# Cyusb3014_-_4.net
KiCad netlist of a schematic drawn in Altium Designer
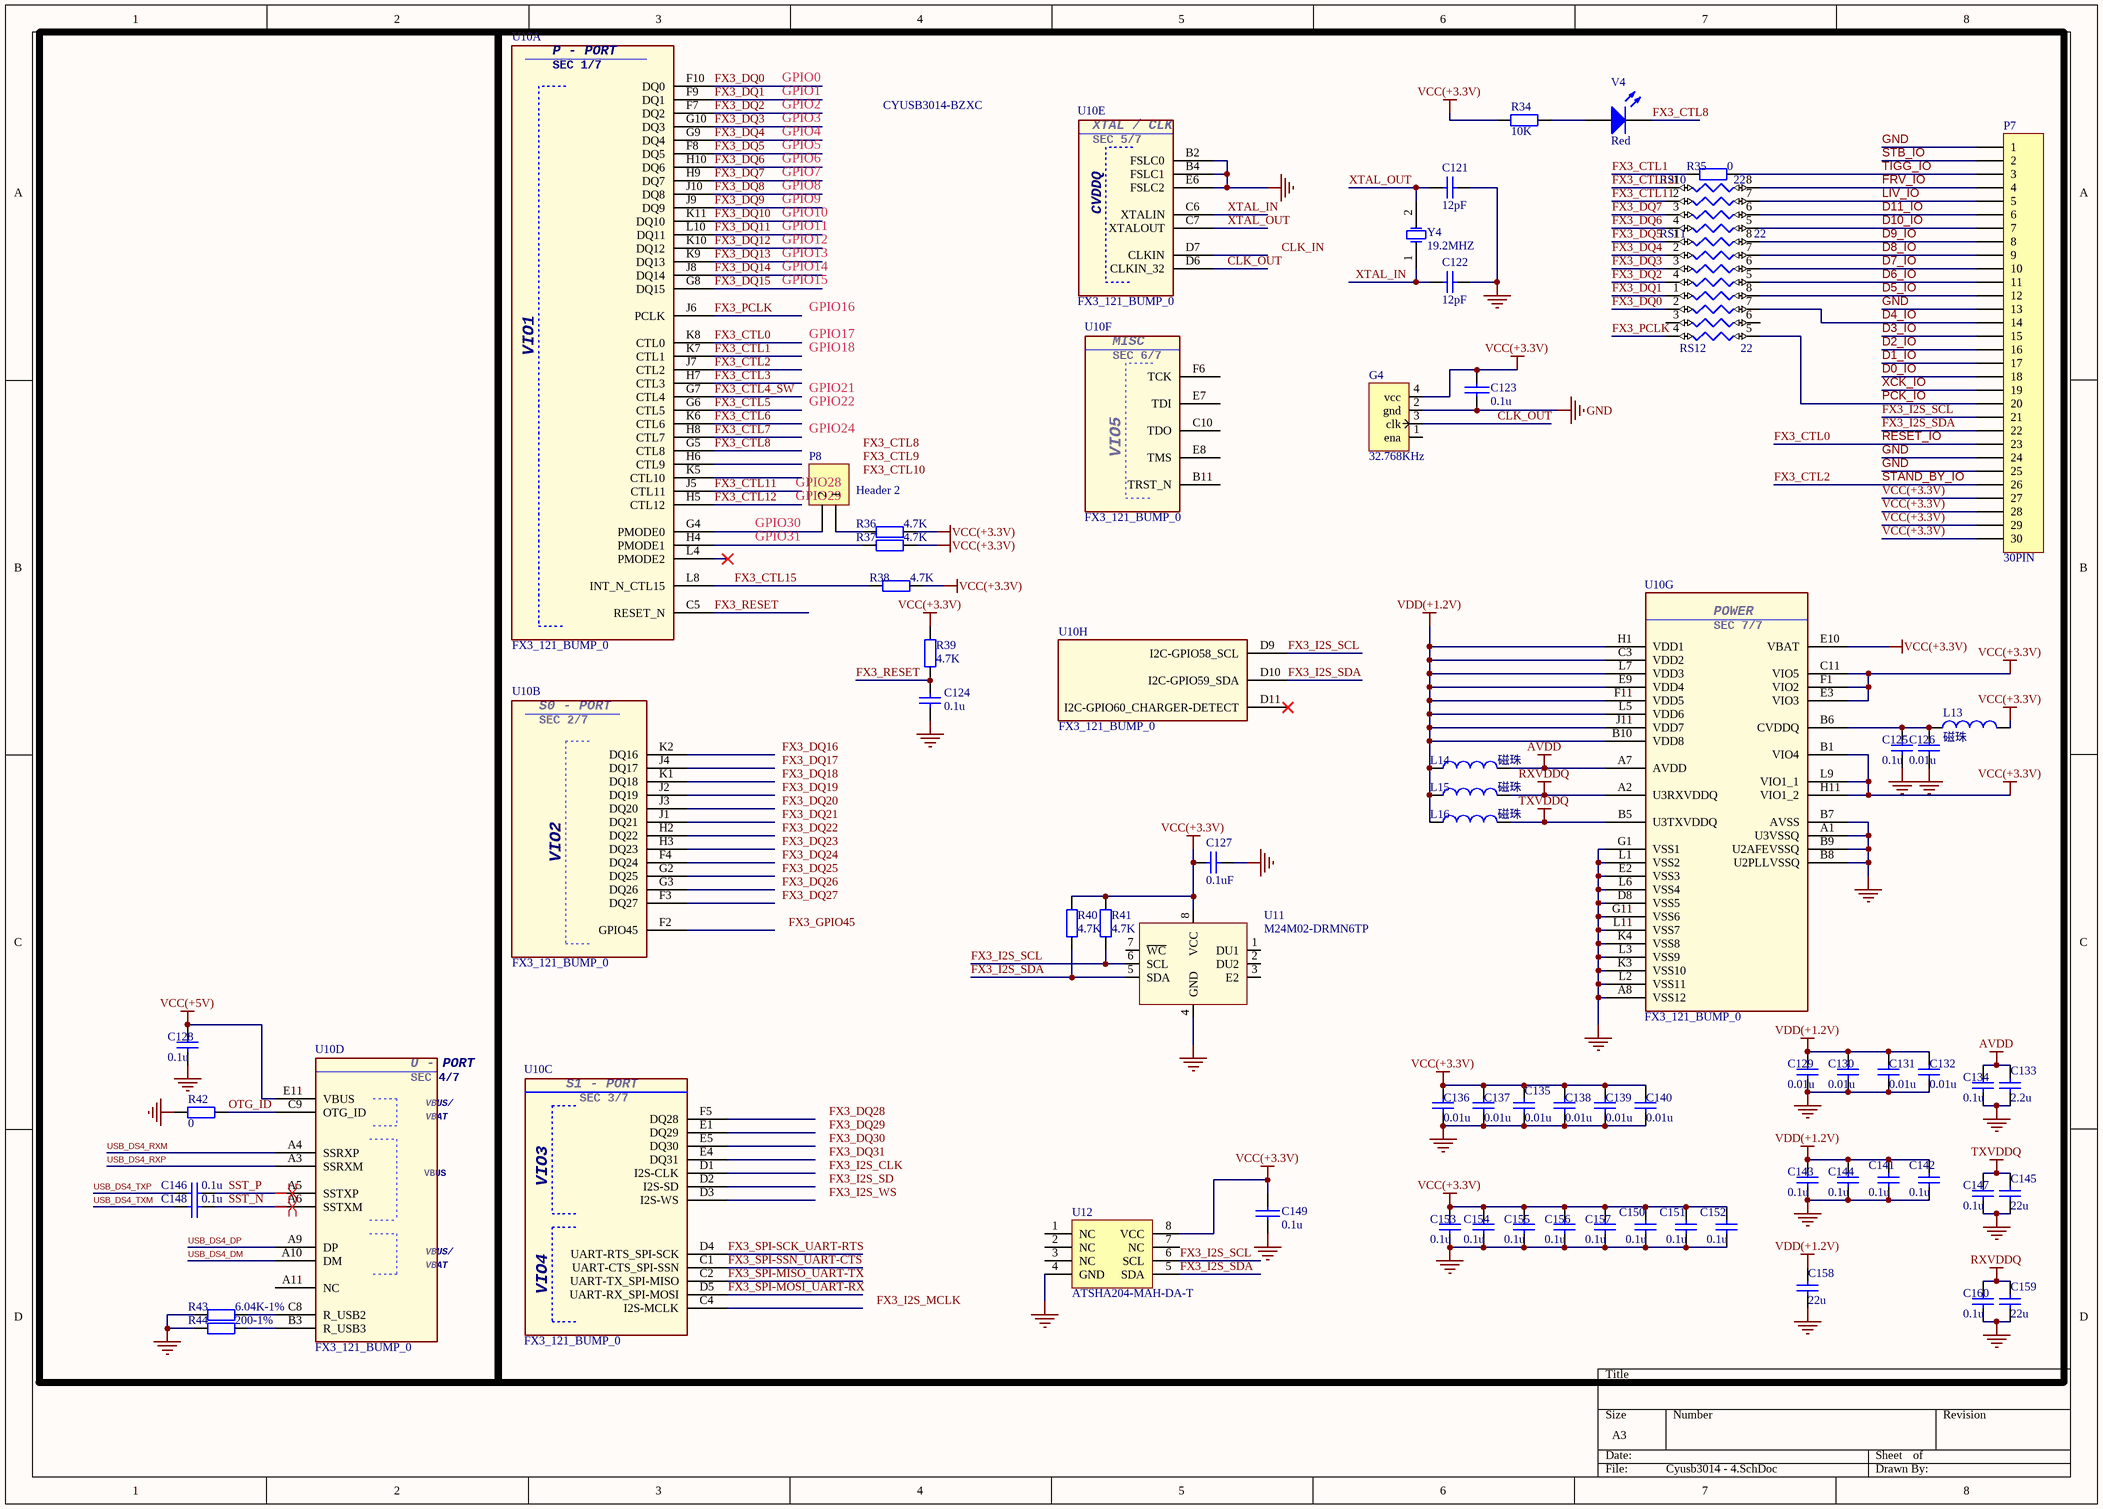
[diagram p0: Cyusb3014 - 4.SchDoc]

(export (version "E")
  (design (tool "Eeschema 10.0.6"))
  (components
    (comp (ref "C121")
      (value "12pF")
      (footprint "0603S-CAP")
      (description "CAP CER SMT 4.3pF 0805")
      (fields
        (field (name "2. MANUFACTURERE PART NUMBER") "C0805C439D5GACTU")
        (field (name "8. ALTERNATE PART") "any")
      )
      (libsource (lib "Peeple_eval") (part "CAP CER SMT 4.3pF 0805"))
    )
    (comp (ref "C122")
      (value "12pF")
      (footprint "0603S-CAP")
      (description "CAP CER SMT 4.3pF 0805")
      (fields
        (field (name "2. MANUFACTURERE PART NUMBER") "C0805C439D5GACTU")
        (field (name "8. ALTERNATE PART") "any")
      )
      (libsource (lib "Peeple_eval") (part "CAP CER SMT 4.3pF 0805"))
    )
    (comp (ref "C123")
      (value "0.1u")
      (footprint "0603S-CAP")
      (description "RC=1206")
      (libsource (lib "*") (part "CAP"))
    )
    (comp (ref "C124")
      (value "0.1u")
      (footprint "0603S-CAP")
      (description "50V/8.2u/0805")
      (fields (field (name "PUBLISHER") "Altium Limited"))
      (libsource (lib "Miscellaneous Devices") (part "Cap"))
    )
    (comp (ref "C125")
      (value "0.1u")
      (footprint "C0402")
      (description "Capacitor")
      (fields (field (name "PUBLISHER") "Altium Limited"))
      (libsource (lib "WM360") (part "CAP0805"))
    )
    (comp (ref "C126")
      (value "0.01u")
      (footprint "C0402")
      (description "Capacitor")
      (fields (field (name "PUBLISHER") "Altium Limited"))
      (libsource (lib "WM360") (part "CAP0805"))
    )
    (comp (ref "C127")
      (value "0.1uF")
      (footprint "0603S-CAP")
      (description "CAP SMT 0.1uF 16V X7R")
      (fields
        (field (name "2. MANUFACTURERE PART NUMBER") "C0805C104K4RACTU")
        (field (name "8. ALTERNATE PART") "any")
      )
      (libsource (lib "Peeple_eval") (part "CAP SMT 0.1uF 16V X7R"))
    )
    (comp (ref "C128")
      (value "0.1u")
      (footprint "C0402")
      (description "Capacitor")
      (fields (field (name "PUBLISHER") "Altium Limited"))
      (libsource (lib "WM360") (part "CAP0805"))
    )
    (comp (ref "C129")
      (value "0.01u")
      (footprint "C0402")
      (description "Capacitor")
      (fields (field (name "PUBLISHER") "Altium Limited"))
      (libsource (lib "WM360") (part "CAP0805"))
    )
    (comp (ref "C130")
      (value "0.01u")
      (footprint "C0402")
      (description "Capacitor")
      (fields (field (name "PUBLISHER") "Altium Limited"))
      (libsource (lib "WM360") (part "CAP0805"))
    )
    (comp (ref "C131")
      (value "0.01u")
      (footprint "C0402")
      (description "Capacitor")
      (fields (field (name "PUBLISHER") "Altium Limited"))
      (libsource (lib "WM360") (part "CAP0805"))
    )
    (comp (ref "C132")
      (value "0.01u")
      (footprint "C0402")
      (description "Capacitor")
      (fields (field (name "PUBLISHER") "Altium Limited"))
      (libsource (lib "WM360") (part "CAP0805"))
    )
    (comp (ref "C133")
      (value "2.2u")
      (footprint "C0805S-CAP")
      (description "Capacitor")
      (fields (field (name "PUBLISHER") "Altium Limited"))
      (libsource (lib "USB_CAMERA") (part "CAP0805"))
    )
    (comp (ref "C134")
      (value "0.1u")
      (footprint "C0402")
      (description "Capacitor")
      (fields (field (name "PUBLISHER") "Altium Limited"))
      (libsource (lib "WM360") (part "CAP0805"))
    )
    (comp (ref "C135")
      (value "0.01u")
      (footprint "C0402")
      (description "Capacitor")
      (fields (field (name "PUBLISHER") "Altium Limited"))
      (libsource (lib "WM360") (part "CAP0805"))
    )
    (comp (ref "C136")
      (value "0.01u")
      (footprint "C0402")
      (description "Capacitor")
      (fields (field (name "PUBLISHER") "Altium Limited"))
      (libsource (lib "WM360") (part "CAP0805"))
    )
    (comp (ref "C137")
      (value "0.01u")
      (footprint "C0402")
      (description "Capacitor")
      (fields (field (name "PUBLISHER") "Altium Limited"))
      (libsource (lib "WM360") (part "CAP0805"))
    )
    (comp (ref "C138")
      (value "0.01u")
      (footprint "C0402")
      (description "Capacitor")
      (fields (field (name "PUBLISHER") "Altium Limited"))
      (libsource (lib "WM360") (part "CAP0805"))
    )
    (comp (ref "C139")
      (value "0.01u")
      (footprint "C0402")
      (description "Capacitor")
      (fields (field (name "PUBLISHER") "Altium Limited"))
      (libsource (lib "WM360") (part "CAP0805"))
    )
    (comp (ref "C140")
      (value "0.01u")
      (footprint "C0402")
      (description "Capacitor")
      (fields (field (name "PUBLISHER") "Altium Limited"))
      (libsource (lib "WM360") (part "CAP0805"))
    )
    (comp (ref "C141")
      (value "0.1u")
      (footprint "C0402")
      (description "Capacitor")
      (fields (field (name "PUBLISHER") "Altium Limited"))
      (libsource (lib "WM360") (part "CAP0805"))
    )
    (comp (ref "C142")
      (value "0.1u")
      (footprint "C0402")
      (description "Capacitor")
      (fields (field (name "PUBLISHER") "Altium Limited"))
      (libsource (lib "WM360") (part "CAP0805"))
    )
    (comp (ref "C143")
      (value "0.1u")
      (footprint "C0402")
      (description "Capacitor")
      (fields (field (name "PUBLISHER") "Altium Limited"))
      (libsource (lib "WM360") (part "CAP0805"))
    )
    (comp (ref "C144")
      (value "0.1u")
      (footprint "C0402")
      (description "Capacitor")
      (fields (field (name "PUBLISHER") "Altium Limited"))
      (libsource (lib "WM360") (part "CAP0805"))
    )
    (comp (ref "C145")
      (value "22u")
      (footprint "C0805S-CAP")
      (description "Capacitor")
      (fields (field (name "PUBLISHER") "Altium Limited"))
      (libsource (lib "USB_CAMERA") (part "CAP0805"))
    )
    (comp (ref "C146")
      (value "0.1u")
      (footprint "C0402")
      (description "Capacitor")
      (fields (field (name "PUBLISHER") "Altium Limited"))
      (libsource (lib "WM360") (part "CAP0805"))
    )
    (comp (ref "C147")
      (value "0.1u")
      (footprint "C0402")
      (description "Capacitor")
      (fields (field (name "PUBLISHER") "Altium Limited"))
      (libsource (lib "WM360") (part "CAP0805"))
    )
    (comp (ref "C148")
      (value "0.1u")
      (footprint "C0402")
      (description "Capacitor")
      (fields (field (name "PUBLISHER") "Altium Limited"))
      (libsource (lib "WM360") (part "CAP0805"))
    )
    (comp (ref "C149")
      (value "0.1u")
      (footprint "0603S-CAP")
      (description "RC=1206")
      (libsource (lib "*") (part "CAP"))
    )
    (comp (ref "C150")
      (value "0.1u")
      (footprint "C0402")
      (description "Capacitor")
      (fields (field (name "PUBLISHER") "Altium Limited"))
      (libsource (lib "WM360") (part "CAP0805"))
    )
    (comp (ref "C151")
      (value "0.1u")
      (footprint "C0402")
      (description "Capacitor")
      (fields (field (name "PUBLISHER") "Altium Limited"))
      (libsource (lib "WM360") (part "CAP0805"))
    )
    (comp (ref "C152")
      (value "0.1u")
      (footprint "C0402")
      (description "Capacitor")
      (fields (field (name "PUBLISHER") "Altium Limited"))
      (libsource (lib "WM360") (part "CAP0805"))
    )
    (comp (ref "C153")
      (value "0.1u")
      (footprint "C0402")
      (description "Capacitor")
      (fields (field (name "PUBLISHER") "Altium Limited"))
      (libsource (lib "WM360") (part "CAP0805"))
    )
    (comp (ref "C154")
      (value "0.1u")
      (footprint "C0402")
      (description "Capacitor")
      (fields (field (name "PUBLISHER") "Altium Limited"))
      (libsource (lib "WM360") (part "CAP0805"))
    )
    (comp (ref "C155")
      (value "0.1u")
      (footprint "C0402")
      (description "Capacitor")
      (fields (field (name "PUBLISHER") "Altium Limited"))
      (libsource (lib "WM360") (part "CAP0805"))
    )
    (comp (ref "C156")
      (value "0.1u")
      (footprint "C0402")
      (description "Capacitor")
      (fields (field (name "PUBLISHER") "Altium Limited"))
      (libsource (lib "WM360") (part "CAP0805"))
    )
    (comp (ref "C157")
      (value "0.1u")
      (footprint "C0402")
      (description "Capacitor")
      (fields (field (name "PUBLISHER") "Altium Limited"))
      (libsource (lib "WM360") (part "CAP0805"))
    )
    (comp (ref "C158")
      (value "22u")
      (footprint "C0805S-CAP")
      (description "Capacitor")
      (fields (field (name "PUBLISHER") "Altium Limited"))
      (libsource (lib "USB_CAMERA") (part "CAP0805"))
    )
    (comp (ref "C159")
      (value "22u")
      (footprint "C0805S-CAP")
      (description "Capacitor")
      (fields (field (name "PUBLISHER") "Altium Limited"))
      (libsource (lib "USB_CAMERA") (part "CAP0805"))
    )
    (comp (ref "C160")
      (value "0.1u")
      (footprint "C0402")
      (description "Capacitor")
      (fields (field (name "PUBLISHER") "Altium Limited"))
      (libsource (lib "WM360") (part "CAP0805"))
    )
    (comp (ref "G4") (value "32.768KHz") (footprint "爱普生晶振3.2×2.5mm") (libsource (lib "*") (part "CTY4-B")))
    (comp (ref "L13")
      (value "磁珠")
      (footprint "L0603")
      (description "Inductor")
      (fields (field (name "PUBLISHER") "Altium Limited"))
      (libsource (lib "Miscellaneous Devices") (part "Inductor"))
    )
    (comp (ref "L14")
      (value "磁珠")
      (footprint "L0603")
      (description "Inductor")
      (fields (field (name "PUBLISHER") "Altium Limited"))
      (libsource (lib "Miscellaneous Devices") (part "Inductor"))
    )
    (comp (ref "L15")
      (value "磁珠")
      (footprint "L0603")
      (description "Inductor")
      (fields (field (name "PUBLISHER") "Altium Limited"))
      (libsource (lib "Miscellaneous Devices") (part "Inductor"))
    )
    (comp (ref "L16")
      (value "磁珠")
      (footprint "L0603")
      (description "Inductor")
      (fields (field (name "PUBLISHER") "Altium Limited"))
      (libsource (lib "Miscellaneous Devices") (part "Inductor"))
    )
    (comp (ref "P7")
      (value "30PIN")
      (footprint "FH12-30S-0.5SH")
      (description "Header, 30-Pin")
      (fields (field (name "PUBLISHER") "Altium Limited"))
      (libsource (lib "Miscellaneous Connectors") (part "Header 30"))
    )
    (comp (ref "P8")
      (value "Header 2")
      (footprint "HDR1X2")
      (description "Header, 2-Pin")
      (fields (field (name "PUBLISHER") "Altium Limited"))
      (libsource (lib "Miscellaneous Connectors") (part "Header 2"))
    )
    (comp (ref "R34")
      (value "10K")
      (footprint "0603S-RES")
      (description "Resistor")
      (fields (field (name "PUBLISHER") "Altium Limited"))
      (libsource (lib "DM642") (part "Res2"))
    )
    (comp (ref "R35")
      (value "0")
      (footprint "0603S-RES")
      (description "Resistor")
      (fields (field (name "PUBLISHER") "Altium Limited"))
      (libsource (lib "DM642") (part "Res2"))
    )
    (comp (ref "R36")
      (value "4.7K")
      (footprint "0603S-RES")
      (description "Resistor")
      (fields (field (name "PUBLISHER") "Altium Limited"))
      (libsource (lib "") (part "Res2_1"))
    )
    (comp (ref "R37")
      (value "4.7K")
      (footprint "0603S-RES")
      (description "Resistor")
      (fields (field (name "PUBLISHER") "Altium Limited"))
      (libsource (lib "") (part "Res2_1"))
    )
    (comp (ref "R38")
      (value "4.7K")
      (footprint "0603S-RES")
      (description "Resistor")
      (fields (field (name "PUBLISHER") "Altium Limited"))
      (libsource (lib "") (part "Res2_2"))
    )
    (comp (ref "R39")
      (value "4.7K")
      (footprint "0603S-RES")
      (description "Resistor")
      (fields (field (name "PUBLISHER") "Altium Limited"))
      (libsource (lib "") (part "Res2_3"))
    )
    (comp (ref "R40")
      (value "4.7K")
      (footprint "0603S-RES")
      (description "Resistor")
      (fields (field (name "PUBLISHER") "Altium Limited"))
      (libsource (lib "") (part "Res2_1"))
    )
    (comp (ref "R41")
      (value "4.7K")
      (footprint "0603S-RES")
      (description "Resistor")
      (fields (field (name "PUBLISHER") "Altium Limited"))
      (libsource (lib "") (part "Res2_1"))
    )
    (comp (ref "R42")
      (value "0")
      (footprint "0603S-RES")
      (description "Resistor")
      (fields (field (name "PUBLISHER") "Altium Limited"))
      (libsource (lib "") (part "Res2_2"))
    )
    (comp (ref "R43")
      (value "6.04K-1%")
      (footprint "0603S-RES")
      (description "Resistor")
      (fields (field (name "PUBLISHER") "Altium Limited"))
      (libsource (lib "") (part "Res2_2"))
    )
    (comp (ref "R44")
      (value "200-1%")
      (footprint "0603S-RES")
      (description "Resistor")
      (fields (field (name "PUBLISHER") "Altium Limited"))
      (libsource (lib "") (part "Res2_2"))
    )
    (comp (ref "RS10") (value "22") (footprint "NC06-4") (libsource (lib "*") (part "RN4")))
    (comp (ref "RS11") (value "22") (footprint "NC06-4") (libsource (lib "*") (part "RN4")))
    (comp (ref "RS12") (value "22") (footprint "NC06-4") (libsource (lib "*") (part "RN4")))
    (comp (ref "U10")
      (value "FX3_121_BUMP_0")
      (footprint "121_BGA_FX3")
      (libsource (lib "USB_CAMERA") (part "FX3_121_BUMP_0"))
    )
    (comp (ref "U11")
      (value "M24M02-DRMN6TP")
      (footprint "SOIC127P600X175-8N")
      (description "IC EEPROM 64KBIT 400KHZ 8SOIC")
      (fields
        (field (name "MANUFACTURER") "Microchip Technology")
        (field (name "MANUFACTURER PART NUMBER") "24LC64-I/SN")
      )
      (libsource (lib "Schlib1") (part "24LC64-I/SN"))
    )
    (comp (ref "U12")
      (value "ATSHA204-MAH-DA-T")
      (footprint "UDFN")
      (libsource (lib "CY7C68013-56") (part "AT24C128"))
    )
    (comp (ref "V4")
      (value "Red")
      (footprint "LED0805S")
      (description "Typical INFRARED GaAs LED")
      (fields (field (name "PUBLISHER") "Altium Limited"))
      (libsource (lib "DM642") (part "LED0"))
    )
    (comp (ref "Y4")
      (value "19.2MHZ")
      (footprint "爱普生晶振3.2×2.5MM - 无源")
      (description "Crystal, CRYSTAL 32.768KHZ 6PF SMD")
      (fields
        (field (name "2. MANUFACTURERE PART NUMBER") "ABS07-120-32.768KHZ-T")
        (field (name "4. SUPPLIER PART NUMBER") "535-11937-1-ND")
      )
      (libsource (lib "Peeple_eval") (part "XTAL 32.768KHZ"))
    )
  )
  (nets
    (net (code "2") (name "/CLK_OUT") (class "Default")
      (node (ref "G4") (pin "3") (pinfunction "clk_3") (pintype "passive"))
      (node (ref "U10") (pin "D6") (pinfunction "CLKIN_32_D6") (pintype "passive"))
    )
    (net (code "3") (name "/D0_IO") (class "Default")
      (node (ref "P7") (pin "18") (pinfunction "18_18") (pintype "passive"))
    )
    (net (code "4") (name "/D1_IO") (class "Default")
      (node (ref "P7") (pin "17") (pinfunction "17_17") (pintype "passive"))
    )
    (net (code "5") (name "/D2_IO") (class "Default")
      (node (ref "P7") (pin "16") (pinfunction "16_16") (pintype "passive"))
    )
    (net (code "6") (name "/D3_IO") (class "Default")
      (node (ref "P7") (pin "15") (pinfunction "15_15") (pintype "passive"))
    )
    (net (code "7") (name "/D4_IO") (class "Default")
      (node (ref "P7") (pin "14") (pinfunction "14_14") (pintype "passive"))
      (node (ref "RS12") (pin "7") (pinfunction "7_7") (pintype "bidirectional"))
    )
    (net (code "8") (name "/D5_IO") (class "Default")
      (node (ref "P7") (pin "12") (pinfunction "12_12") (pintype "passive"))
      (node (ref "RS12") (pin "8") (pinfunction "8_8") (pintype "bidirectional"))
    )
    (net (code "9") (name "/D6_IO") (class "Default")
      (node (ref "P7") (pin "11") (pinfunction "11_11") (pintype "passive"))
      (node (ref "RS11") (pin "5") (pinfunction "5_5") (pintype "bidirectional"))
    )
    (net (code "10") (name "/D7_IO") (class "Default")
      (node (ref "P7") (pin "10") (pinfunction "10_10") (pintype "passive"))
      (node (ref "RS11") (pin "6") (pinfunction "6_6") (pintype "bidirectional"))
    )
    (net (code "11") (name "/D8_IO") (class "Default")
      (node (ref "P7") (pin "9") (pinfunction "9_9") (pintype "passive"))
      (node (ref "RS11") (pin "7") (pinfunction "7_7") (pintype "bidirectional"))
    )
    (net (code "12") (name "/D9_IO") (class "Default")
      (node (ref "P7") (pin "8") (pinfunction "8_8") (pintype "passive"))
      (node (ref "RS11") (pin "8") (pinfunction "8_8") (pintype "bidirectional"))
    )
    (net (code "13") (name "/D10_IO") (class "Default")
      (node (ref "P7") (pin "7") (pinfunction "7_7") (pintype "passive"))
      (node (ref "RS10") (pin "5") (pinfunction "5_5") (pintype "bidirectional"))
    )
    (net (code "14") (name "/D11_IO") (class "Default")
      (node (ref "P7") (pin "6") (pinfunction "6_6") (pintype "passive"))
      (node (ref "RS10") (pin "6") (pinfunction "6_6") (pintype "bidirectional"))
    )
    (net (code "15") (name "/FRV_IO") (class "Default")
      (node (ref "P7") (pin "4") (pinfunction "4_4") (pintype "passive"))
      (node (ref "RS10") (pin "8") (pinfunction "8_8") (pintype "bidirectional"))
    )
    (net (code "16") (name "/FX3_CTL0") (class "Default")
      (node (ref "P7") (pin "23") (pinfunction "23_23") (pintype "passive"))
      (node (ref "U10") (pin "K8") (pinfunction "CTL0_K8") (pintype "passive"))
    )
    (net (code "17") (name "/FX3_CTL1") (class "Default")
      (node (ref "R35") (pin "2") (pinfunction "2_2") (pintype "passive"))
      (node (ref "U10") (pin "K7") (pinfunction "CTL1_K7") (pintype "passive"))
    )
    (net (code "18") (name "/FX3_CTL2") (class "Default")
      (node (ref "P7") (pin "26") (pinfunction "26_26") (pintype "passive"))
      (node (ref "U10") (pin "J7") (pinfunction "CTL2_J7") (pintype "passive"))
    )
    (net (code "19") (name "/FX3_CTL3") (class "Default")
      (node (ref "U10") (pin "H7") (pinfunction "CTL3_H7") (pintype "passive"))
    )
    (net (code "20") (name "/FX3_CTL4_SW") (class "Default")
      (node (ref "U10") (pin "G7") (pinfunction "CTL4_G7") (pintype "passive"))
    )
    (net (code "21") (name "/FX3_CTL5") (class "Default")
      (node (ref "U10") (pin "G6") (pinfunction "CTL5_G6") (pintype "passive"))
    )
    (net (code "22") (name "/FX3_CTL6") (class "Default")
      (node (ref "U10") (pin "K6") (pinfunction "CTL6_K6") (pintype "passive"))
    )
    (net (code "23") (name "/FX3_CTL7") (class "Default")
      (node (ref "U10") (pin "H8") (pinfunction "CTL7_H8") (pintype "passive"))
    )
    (net (code "24") (name "/FX3_CTL8") (class "Default")
      (node (ref "U10") (pin "G5") (pinfunction "CTL8_G5") (pintype "passive"))
      (node (ref "V4") (pin "2") (pinfunction "K_2") (pintype "passive"))
    )
    (net (code "27") (name "/FX3_CTL11") (class "Default")
      (node (ref "RS10") (pin "2") (pinfunction "2_2") (pintype "bidirectional"))
      (node (ref "U10") (pin "J5") (pinfunction "CTL11_J5") (pintype "passive"))
    )
    (net (code "28") (name "/FX3_CTL12") (class "Default")
      (node (ref "RS10") (pin "1") (pinfunction "1_1") (pintype "bidirectional"))
      (node (ref "U10") (pin "H5") (pinfunction "CTL12_H5") (pintype "passive"))
    )
    (net (code "29") (name "/FX3_CTL15") (class "Default")
      (node (ref "R38") (pin "2") (pinfunction "2_2") (pintype "passive"))
      (node (ref "U10") (pin "L8") (pinfunction "INT_N_CTL15_L8") (pintype "passive"))
    )
    (net (code "30") (name "/FX3_DQ0") (class "Default")
      (node (ref "RS12") (pin "2") (pinfunction "2_2") (pintype "bidirectional"))
      (node (ref "U10") (pin "F10") (pinfunction "DQ0_F10") (pintype "passive"))
    )
    (net (code "31") (name "/FX3_DQ1") (class "Default")
      (node (ref "RS12") (pin "1") (pinfunction "1_1") (pintype "bidirectional"))
      (node (ref "U10") (pin "F9") (pinfunction "DQ1_F9") (pintype "passive"))
    )
    (net (code "32") (name "/FX3_DQ2") (class "Default")
      (node (ref "RS11") (pin "4") (pinfunction "4_4") (pintype "bidirectional"))
      (node (ref "U10") (pin "F7") (pinfunction "DQ2_F7") (pintype "passive"))
    )
    (net (code "33") (name "/FX3_DQ3") (class "Default")
      (node (ref "RS11") (pin "3") (pinfunction "3_3") (pintype "bidirectional"))
      (node (ref "U10") (pin "G10") (pinfunction "DQ3_G10") (pintype "passive"))
    )
    (net (code "34") (name "/FX3_DQ4") (class "Default")
      (node (ref "RS11") (pin "2") (pinfunction "2_2") (pintype "bidirectional"))
      (node (ref "U10") (pin "G9") (pinfunction "DQ4_G9") (pintype "passive"))
    )
    (net (code "35") (name "/FX3_DQ5") (class "Default")
      (node (ref "RS11") (pin "1") (pinfunction "1_1") (pintype "bidirectional"))
      (node (ref "U10") (pin "F8") (pinfunction "DQ5_F8") (pintype "passive"))
    )
    (net (code "36") (name "/FX3_DQ6") (class "Default")
      (node (ref "RS10") (pin "4") (pinfunction "4_4") (pintype "bidirectional"))
      (node (ref "U10") (pin "H10") (pinfunction "DQ6_H10") (pintype "passive"))
    )
    (net (code "37") (name "/FX3_DQ7") (class "Default")
      (node (ref "RS10") (pin "3") (pinfunction "3_3") (pintype "bidirectional"))
      (node (ref "U10") (pin "H9") (pinfunction "DQ7_H9") (pintype "passive"))
    )
    (net (code "38") (name "/FX3_DQ8") (class "Default")
      (node (ref "U10") (pin "J10") (pinfunction "DQ8_J10") (pintype "passive"))
    )
    (net (code "39") (name "/FX3_DQ9") (class "Default")
      (node (ref "U10") (pin "J9") (pinfunction "DQ9_J9") (pintype "passive"))
    )
    (net (code "40") (name "/FX3_DQ10") (class "Default")
      (node (ref "U10") (pin "K11") (pinfunction "DQ10_K11") (pintype "passive"))
    )
    (net (code "41") (name "/FX3_DQ11") (class "Default")
      (node (ref "U10") (pin "L10") (pinfunction "DQ11_L10") (pintype "passive"))
    )
    (net (code "42") (name "/FX3_DQ12") (class "Default")
      (node (ref "U10") (pin "K10") (pinfunction "DQ12_K10") (pintype "passive"))
    )
    (net (code "43") (name "/FX3_DQ13") (class "Default")
      (node (ref "U10") (pin "K9") (pinfunction "DQ13_K9") (pintype "passive"))
    )
    (net (code "44") (name "/FX3_DQ14") (class "Default")
      (node (ref "U10") (pin "J8") (pinfunction "DQ14_J8") (pintype "passive"))
    )
    (net (code "45") (name "/FX3_DQ15") (class "Default")
      (node (ref "U10") (pin "G8") (pinfunction "DQ15_G8") (pintype "passive"))
    )
    (net (code "65") (name "/FX3_I2S_SCL") (class "Default")
      (node (ref "P7") (pin "21") (pinfunction "21_21") (pintype "passive"))
      (node (ref "R41") (pin "1") (pinfunction "1_1") (pintype "passive"))
      (node (ref "U10") (pin "D9") (pinfunction "I2C-GPIO58_SCL_D9") (pintype "passive"))
      (node (ref "U11") (pin "6") (pinfunction "SCL_6") (pintype "passive"))
      (node (ref "U12") (pin "6") (pinfunction "SCL_6") (pintype "passive"))
    )
    (net (code "67") (name "/FX3_I2S_SDA") (class "Default")
      (node (ref "P7") (pin "22") (pinfunction "22_22") (pintype "passive"))
      (node (ref "R40") (pin "1") (pinfunction "1_1") (pintype "passive"))
      (node (ref "U10") (pin "D10") (pinfunction "I2C-GPIO59_SDA_D10") (pintype "passive"))
      (node (ref "U11") (pin "5") (pinfunction "SDA_5") (pintype "passive"))
      (node (ref "U12") (pin "5") (pinfunction "SDA_5") (pintype "passive"))
    )
    (net (code "69") (name "/FX3_PCLK") (class "Default")
      (node (ref "RS12") (pin "4") (pinfunction "4_4") (pintype "bidirectional"))
      (node (ref "U10") (pin "J6") (pinfunction "PCLK_J6") (pintype "passive"))
    )
    (net (code "70") (name "/FX3_RESET") (class "Default")
      (node (ref "C124") (pin "2") (pinfunction "2_2") (pintype "passive"))
      (node (ref "R39") (pin "2") (pinfunction "2_2") (pintype "passive"))
      (node (ref "U10") (pin "C5") (pinfunction "RESET_N_C5") (pintype "passive"))
    )
    (net (code "71") (name "/FX3_SPI-MISO_UART-TX") (class "Default")
      (node (ref "U10") (pin "C2") (pinfunction "UART-TX_SPI-MISO_C2") (pintype "passive"))
    )
    (net (code "72") (name "/FX3_SPI-MOSI_UART-RX") (class "Default")
      (node (ref "U10") (pin "D5") (pinfunction "UART-RX_SPI-MOSI_D5") (pintype "passive"))
    )
    (net (code "73") (name "/FX3_SPI-SCK_UART-RTS") (class "Default")
      (node (ref "U10") (pin "D4") (pinfunction "UART-RTS_SPI-SCK_D4") (pintype "passive"))
    )
    (net (code "74") (name "/FX3_SPI-SSN_UART-CTS") (class "Default")
      (node (ref "U10") (pin "C1") (pinfunction "UART-CTS_SPI-SSN_C1") (pintype "passive"))
    )
    (net (code "75") (name "/LIV_IO") (class "Default")
      (node (ref "P7") (pin "5") (pinfunction "5_5") (pintype "passive"))
      (node (ref "RS10") (pin "7") (pinfunction "7_7") (pintype "bidirectional"))
    )
    (net (code "76") (name "/OTG_ID") (class "Default")
      (node (ref "R42") (pin "1") (pinfunction "1_1") (pintype "passive"))
      (node (ref "U10") (pin "C9") (pinfunction "OTG_ID_C9") (pintype "passive"))
    )
    (net (code "77") (name "/PCK_IO") (class "Default")
      (node (ref "P7") (pin "20") (pinfunction "20_20") (pintype "passive"))
      (node (ref "RS12") (pin "5") (pinfunction "5_5") (pintype "bidirectional"))
    )
    (net (code "78") (name "/SST_N") (class "Default")
      (node (ref "C148") (pin "2") (pinfunction "2_2") (pintype "passive"))
      (node (ref "U10") (pin "A6") (pinfunction "SSTXM_A6") (pintype "passive"))
    )
    (net (code "79") (name "/SST_P") (class "Default")
      (node (ref "C146") (pin "2") (pinfunction "2_2") (pintype "passive"))
      (node (ref "U10") (pin "A5") (pinfunction "SSTXP_A5") (pintype "passive"))
    )
    (net (code "80") (name "/STB_IO") (class "Default")
      (node (ref "P7") (pin "2") (pinfunction "2_2") (pintype "passive"))
    )
    (net (code "81") (name "/TIGG_IO") (class "Default")
      (node (ref "P7") (pin "3") (pinfunction "3_3") (pintype "passive"))
      (node (ref "R35") (pin "1") (pinfunction "1_1") (pintype "passive"))
    )
    (net (code "82") (name "/USB_DS4_DM") (class "Default")
      (node (ref "U10") (pin "A10") (pinfunction "DM_A10") (pintype "passive"))
    )
    (net (code "83") (name "/USB_DS4_DP") (class "Default")
      (node (ref "U10") (pin "A9") (pinfunction "DP_A9") (pintype "passive"))
    )
    (net (code "84") (name "/USB_DS4_RXM") (class "Default")
      (node (ref "U10") (pin "A4") (pinfunction "SSRXP_A4") (pintype "passive"))
    )
    (net (code "85") (name "/USB_DS4_RXP") (class "Default")
      (node (ref "U10") (pin "A3") (pinfunction "SSRXM_A3") (pintype "passive"))
    )
    (net (code "86") (name "/USB_DS4_TXM") (class "Default")
      (node (ref "C148") (pin "1") (pinfunction "1_1") (pintype "passive"))
    )
    (net (code "87") (name "/USB_DS4_TXP") (class "Default")
      (node (ref "C146") (pin "1") (pinfunction "1_1") (pintype "passive"))
    )
    (net (code "88") (name "/XCK_IO") (class "Default")
      (node (ref "P7") (pin "19") (pinfunction "19_19") (pintype "passive"))
    )
    (net (code "89") (name "/XTAL_IN") (class "Default")
      (node (ref "C122") (pin "2") (pinfunction "2_2") (pintype "passive"))
      (node (ref "U10") (pin "C6") (pinfunction "XTALIN_C6") (pintype "passive"))
      (node (ref "Y4") (pin "1") (pinfunction "OSC1_1") (pintype "passive"))
    )
    (net (code "90") (name "/XTAL_OUT") (class "Default")
      (node (ref "C121") (pin "2") (pinfunction "2_2") (pintype "passive"))
      (node (ref "U10") (pin "C7") (pinfunction "XTALOUT_C7") (pintype "passive"))
      (node (ref "Y4") (pin "2") (pinfunction "OSC2_2") (pintype "passive"))
    )
    (net (code "91") (name "AVDD") (class "Default")
      (node (ref "C133") (pin "2") (pinfunction "2_2") (pintype "passive"))
      (node (ref "C134") (pin "1") (pinfunction "1_1") (pintype "passive"))
      (node (ref "L14") (pin "2") (pinfunction "2_2") (pintype "passive"))
      (node (ref "U10") (pin "A7") (pinfunction "AVDD_A7") (pintype "passive"))
    )
    (net (code "92") (name "GND") (class "Default")
      (node (ref "C121") (pin "1") (pinfunction "1_1") (pintype "passive"))
      (node (ref "C122") (pin "1") (pinfunction "1_1") (pintype "passive"))
      (node (ref "C123") (pin "2") (pintype "passive"))
      (node (ref "C124") (pin "1") (pinfunction "1_1") (pintype "passive"))
      (node (ref "C125") (pin "2") (pinfunction "2_2") (pintype "passive"))
      (node (ref "C126") (pin "2") (pinfunction "2_2") (pintype "passive"))
      (node (ref "C127") (pin "1") (pinfunction "1_1") (pintype "passive"))
      (node (ref "C128") (pin "2") (pinfunction "2_2") (pintype "passive"))
      (node (ref "C129") (pin "2") (pinfunction "2_2") (pintype "passive"))
      (node (ref "C130") (pin "2") (pinfunction "2_2") (pintype "passive"))
      (node (ref "C131") (pin "2") (pinfunction "2_2") (pintype "passive"))
      (node (ref "C132") (pin "2") (pinfunction "2_2") (pintype "passive"))
      (node (ref "C133") (pin "1") (pinfunction "1_1") (pintype "passive"))
      (node (ref "C134") (pin "2") (pinfunction "2_2") (pintype "passive"))
      (node (ref "C135") (pin "2") (pinfunction "2_2") (pintype "passive"))
      (node (ref "C136") (pin "2") (pinfunction "2_2") (pintype "passive"))
      (node (ref "C137") (pin "2") (pinfunction "2_2") (pintype "passive"))
      (node (ref "C138") (pin "2") (pinfunction "2_2") (pintype "passive"))
      (node (ref "C139") (pin "2") (pinfunction "2_2") (pintype "passive"))
      (node (ref "C140") (pin "2") (pinfunction "2_2") (pintype "passive"))
      (node (ref "C141") (pin "2") (pinfunction "2_2") (pintype "passive"))
      (node (ref "C142") (pin "2") (pinfunction "2_2") (pintype "passive"))
      (node (ref "C143") (pin "2") (pinfunction "2_2") (pintype "passive"))
      (node (ref "C144") (pin "2") (pinfunction "2_2") (pintype "passive"))
      (node (ref "C145") (pin "1") (pinfunction "1_1") (pintype "passive"))
      (node (ref "C147") (pin "2") (pinfunction "2_2") (pintype "passive"))
      (node (ref "C149") (pin "2") (pintype "passive"))
      (node (ref "C150") (pin "2") (pinfunction "2_2") (pintype "passive"))
      (node (ref "C151") (pin "2") (pinfunction "2_2") (pintype "passive"))
      (node (ref "C152") (pin "2") (pinfunction "2_2") (pintype "passive"))
      (node (ref "C153") (pin "2") (pinfunction "2_2") (pintype "passive"))
      (node (ref "C154") (pin "2") (pinfunction "2_2") (pintype "passive"))
      (node (ref "C155") (pin "2") (pinfunction "2_2") (pintype "passive"))
      (node (ref "C156") (pin "2") (pinfunction "2_2") (pintype "passive"))
      (node (ref "C157") (pin "2") (pinfunction "2_2") (pintype "passive"))
      (node (ref "C158") (pin "1") (pinfunction "1_1") (pintype "passive"))
      (node (ref "C159") (pin "1") (pinfunction "1_1") (pintype "passive"))
      (node (ref "C160") (pin "2") (pinfunction "2_2") (pintype "passive"))
      (node (ref "G4") (pin "2") (pinfunction "gnd_2") (pintype "power_in"))
      (node (ref "P7") (pin "1") (pinfunction "1_1") (pintype "passive"))
      (node (ref "P7") (pin "13") (pinfunction "13_13") (pintype "passive"))
      (node (ref "P7") (pin "24") (pinfunction "24_24") (pintype "passive"))
      (node (ref "P7") (pin "25") (pinfunction "25_25") (pintype "passive"))
      (node (ref "R42") (pin "2") (pinfunction "2_2") (pintype "passive"))
      (node (ref "R43") (pin "2") (pinfunction "2_2") (pintype "passive"))
      (node (ref "R44") (pin "2") (pinfunction "2_2") (pintype "passive"))
      (node (ref "U10") (pin "A1") (pinfunction "U3VSSQ_A1") (pintype "passive"))
      (node (ref "U10") (pin "A8") (pinfunction "VSS12_A8") (pintype "passive"))
      (node (ref "U10") (pin "B2") (pinfunction "FSLC0_B2") (pintype "passive"))
      (node (ref "U10") (pin "B4") (pinfunction "FSLC1_B4") (pintype "passive"))
      (node (ref "U10") (pin "B7") (pinfunction "AVSS_B7") (pintype "passive"))
      (node (ref "U10") (pin "B8") (pinfunction "U2PLLVSSQ_B8") (pintype "passive"))
      (node (ref "U10") (pin "B9") (pinfunction "U2AFEVSSQ_B9") (pintype "passive"))
      (node (ref "U10") (pin "D8") (pinfunction "VSS5_D8") (pintype "passive"))
      (node (ref "U10") (pin "E2") (pinfunction "VSS3_E2") (pintype "passive"))
      (node (ref "U10") (pin "E6") (pinfunction "FSLC2_E6") (pintype "passive"))
      (node (ref "U10") (pin "G1") (pinfunction "VSS1_G1") (pintype "passive"))
      (node (ref "U10") (pin "G11") (pinfunction "VSS6_G11") (pintype "passive"))
      (node (ref "U10") (pin "K3") (pinfunction "VSS10_K3") (pintype "passive"))
      (node (ref "U10") (pin "K4") (pinfunction "VSS8_K4") (pintype "passive"))
      (node (ref "U10") (pin "L1") (pinfunction "VSS2_L1") (pintype "passive"))
      (node (ref "U10") (pin "L11") (pinfunction "VSS7_L11") (pintype "passive"))
      (node (ref "U10") (pin "L2") (pinfunction "VSS11_L2") (pintype "passive"))
      (node (ref "U10") (pin "L3") (pinfunction "VSS9_L3") (pintype "passive"))
      (node (ref "U10") (pin "L6") (pinfunction "VSS4_L6") (pintype "passive"))
      (node (ref "U11") (pin "4") (pinfunction "GND_4") (pintype "passive"))
      (node (ref "U12") (pin "4") (pinfunction "GND_4") (pintype "passive"))
    )
    (net (code "93") (name "Net-(P8-Pad1)") (class "Default")
      (node (ref "P8") (pin "1") (pinfunction "1_1") (pintype "passive"))
      (node (ref "R36") (pin "1") (pinfunction "1_1") (pintype "passive"))
    )
    (net (code "94") (name "Net-(U10A-PMODE0)") (class "Default")
      (node (ref "P8") (pin "2") (pinfunction "2_2") (pintype "passive"))
      (node (ref "U10") (pin "G4") (pinfunction "PMODE0_G4") (pintype "passive"))
    )
    (net (code "95") (name "Net-(U10A-PMODE1)") (class "Default")
      (node (ref "R37") (pin "1") (pinfunction "1_1") (pintype "passive"))
      (node (ref "U10") (pin "H4") (pinfunction "PMODE1_H4") (pintype "passive"))
    )
    (net (code "96") (name "Net-(U10D-R_USB2)") (class "Default")
      (node (ref "R43") (pin "1") (pinfunction "1_1") (pintype "passive"))
      (node (ref "U10") (pin "C8") (pinfunction "R_USB2_C8") (pintype "passive"))
    )
    (net (code "97") (name "Net-(U10D-R_USB3)") (class "Default")
      (node (ref "R44") (pin "1") (pinfunction "1_1") (pintype "passive"))
      (node (ref "U10") (pin "B3") (pinfunction "R_USB3_B3") (pintype "passive"))
    )
    (net (code "98") (name "Net-(U10G-CVDDQ)") (class "Default")
      (node (ref "C125") (pin "1") (pinfunction "1_1") (pintype "passive"))
      (node (ref "C126") (pin "1") (pinfunction "1_1") (pintype "passive"))
      (node (ref "L13") (pin "1") (pinfunction "1_1") (pintype "passive"))
      (node (ref "U10") (pin "B6") (pinfunction "CVDDQ_B6") (pintype "passive"))
    )
    (net (code "99") (name "Net-(V4-A)") (class "Default")
      (node (ref "R34") (pin "1") (pinfunction "1_1") (pintype "passive"))
      (node (ref "V4") (pin "1") (pinfunction "A_1") (pintype "passive"))
    )
    (net (code "100") (name "RXVDDQ") (class "Default")
      (node (ref "C159") (pin "2") (pinfunction "2_2") (pintype "passive"))
      (node (ref "C160") (pin "1") (pinfunction "1_1") (pintype "passive"))
      (node (ref "L15") (pin "2") (pinfunction "2_2") (pintype "passive"))
      (node (ref "U10") (pin "A2") (pinfunction "U3RXVDDQ_A2") (pintype "passive"))
    )
    (net (code "101") (name "TXVDDQ") (class "Default")
      (node (ref "C145") (pin "2") (pinfunction "2_2") (pintype "passive"))
      (node (ref "C147") (pin "1") (pinfunction "1_1") (pintype "passive"))
      (node (ref "L16") (pin "2") (pinfunction "2_2") (pintype "passive"))
      (node (ref "U10") (pin "B5") (pinfunction "U3TXVDDQ_B5") (pintype "passive"))
    )
    (net (code "102") (name "VCC(+3.3V)") (class "Default")
      (node (ref "C123") (pin "1") (pintype "passive"))
      (node (ref "C127") (pin "2") (pinfunction "2_2") (pintype "passive"))
      (node (ref "C135") (pin "1") (pinfunction "1_1") (pintype "passive"))
      (node (ref "C136") (pin "1") (pinfunction "1_1") (pintype "passive"))
      (node (ref "C137") (pin "1") (pinfunction "1_1") (pintype "passive"))
      (node (ref "C138") (pin "1") (pinfunction "1_1") (pintype "passive"))
      (node (ref "C139") (pin "1") (pinfunction "1_1") (pintype "passive"))
      (node (ref "C140") (pin "1") (pinfunction "1_1") (pintype "passive"))
      (node (ref "C149") (pin "1") (pintype "passive"))
      (node (ref "C150") (pin "1") (pinfunction "1_1") (pintype "passive"))
      (node (ref "C151") (pin "1") (pinfunction "1_1") (pintype "passive"))
      (node (ref "C152") (pin "1") (pinfunction "1_1") (pintype "passive"))
      (node (ref "C153") (pin "1") (pinfunction "1_1") (pintype "passive"))
      (node (ref "C154") (pin "1") (pinfunction "1_1") (pintype "passive"))
      (node (ref "C155") (pin "1") (pinfunction "1_1") (pintype "passive"))
      (node (ref "C156") (pin "1") (pinfunction "1_1") (pintype "passive"))
      (node (ref "C157") (pin "1") (pinfunction "1_1") (pintype "passive"))
      (node (ref "G4") (pin "4") (pinfunction "vcc_4") (pintype "power_in"))
      (node (ref "L13") (pin "2") (pinfunction "2_2") (pintype "passive"))
      (node (ref "P7") (pin "27") (pinfunction "27_27") (pintype "passive"))
      (node (ref "P7") (pin "28") (pinfunction "28_28") (pintype "passive"))
      (node (ref "P7") (pin "29") (pinfunction "29_29") (pintype "passive"))
      (node (ref "P7") (pin "30") (pinfunction "30_30") (pintype "passive"))
      (node (ref "R34") (pin "2") (pinfunction "2_2") (pintype "passive"))
      (node (ref "R36") (pin "2") (pinfunction "2_2") (pintype "passive"))
      (node (ref "R37") (pin "2") (pinfunction "2_2") (pintype "passive"))
      (node (ref "R38") (pin "1") (pinfunction "1_1") (pintype "passive"))
      (node (ref "R39") (pin "1") (pinfunction "1_1") (pintype "passive"))
      (node (ref "R40") (pin "2") (pinfunction "2_2") (pintype "passive"))
      (node (ref "R41") (pin "2") (pinfunction "2_2") (pintype "passive"))
      (node (ref "U10") (pin "B1") (pinfunction "VIO4_B1") (pintype "passive"))
      (node (ref "U10") (pin "C11") (pinfunction "VIO5_C11") (pintype "passive"))
      (node (ref "U10") (pin "E10") (pinfunction "VBAT_E10") (pintype "passive"))
      (node (ref "U10") (pin "E3") (pinfunction "VIO3_E3") (pintype "passive"))
      (node (ref "U10") (pin "F1") (pinfunction "VIO2_F1") (pintype "passive"))
      (node (ref "U10") (pin "H11") (pinfunction "VIO1_2_H11") (pintype "passive"))
      (node (ref "U10") (pin "L9") (pinfunction "VIO1_1_L9") (pintype "passive"))
      (node (ref "U11") (pin "8") (pinfunction "VCC_8") (pintype "passive"))
      (node (ref "U12") (pin "8") (pinfunction "VCC_8") (pintype "passive"))
    )
    (net (code "103") (name "VCC(+5V)") (class "Default")
      (node (ref "C128") (pin "1") (pinfunction "1_1") (pintype "passive"))
      (node (ref "U10") (pin "E11") (pinfunction "VBUS_E11") (pintype "passive"))
    )
    (net (code "104") (name "VDD(+1.2V)") (class "Default")
      (node (ref "C129") (pin "1") (pinfunction "1_1") (pintype "passive"))
      (node (ref "C130") (pin "1") (pinfunction "1_1") (pintype "passive"))
      (node (ref "C131") (pin "1") (pinfunction "1_1") (pintype "passive"))
      (node (ref "C132") (pin "1") (pinfunction "1_1") (pintype "passive"))
      (node (ref "C141") (pin "1") (pinfunction "1_1") (pintype "passive"))
      (node (ref "C142") (pin "1") (pinfunction "1_1") (pintype "passive"))
      (node (ref "C143") (pin "1") (pinfunction "1_1") (pintype "passive"))
      (node (ref "C144") (pin "1") (pinfunction "1_1") (pintype "passive"))
      (node (ref "C158") (pin "2") (pinfunction "2_2") (pintype "passive"))
      (node (ref "L14") (pin "1") (pinfunction "1_1") (pintype "passive"))
      (node (ref "L15") (pin "1") (pinfunction "1_1") (pintype "passive"))
      (node (ref "L16") (pin "1") (pinfunction "1_1") (pintype "passive"))
      (node (ref "U10") (pin "B10") (pinfunction "VDD8_B10") (pintype "passive"))
      (node (ref "U10") (pin "C3") (pinfunction "VDD2_C3") (pintype "passive"))
      (node (ref "U10") (pin "E9") (pinfunction "VDD4_E9") (pintype "passive"))
      (node (ref "U10") (pin "F11") (pinfunction "VDD5_F11") (pintype "passive"))
      (node (ref "U10") (pin "H1") (pinfunction "VDD1_H1") (pintype "passive"))
      (node (ref "U10") (pin "J11") (pinfunction "VDD7_J11") (pintype "passive"))
      (node (ref "U10") (pin "L5") (pinfunction "VDD6_L5") (pintype "passive"))
      (node (ref "U10") (pin "L7") (pinfunction "VDD3_L7") (pintype "passive"))
    )
    (net (code "105") (name "unconnected-(G4-ena-Pad1)") (class "Default")
      (node (ref "G4") (pin "1") (pinfunction "ena_1") (pintype "passive"))
    )
    (net (code "106") (name "unconnected-(RS12-Pad3)") (class "Default")
      (node (ref "RS12") (pin "3") (pinfunction "3_3") (pintype "bidirectional"))
    )
    (net (code "107") (name "unconnected-(RS12-Pad6)") (class "Default")
      (node (ref "RS12") (pin "6") (pinfunction "6_6") (pintype "bidirectional"))
    )
    (net (code "108") (name "unconnected-(U10A-CTL9-PadH6)") (class "Default")
      (node (ref "U10") (pin "H6") (pinfunction "CTL9_H6") (pintype "passive"))
    )
    (net (code "109") (name "unconnected-(U10A-CTL10-PadK5)") (class "Default")
      (node (ref "U10") (pin "K5") (pinfunction "CTL10_K5") (pintype "passive"))
    )
    (net (code "110") (name "unconnected-(U10A-PMODE2-PadL4)") (class "Default")
      (node (ref "U10") (pin "L4") (pinfunction "PMODE2_L4") (pintype "passive+no_connect"))
    )
    (net (code "111") (name "unconnected-(U10B-DQ16-PadK2)") (class "Default")
      (node (ref "U10") (pin "K2") (pinfunction "DQ16_K2") (pintype "passive"))
    )
    (net (code "112") (name "unconnected-(U10B-DQ17-PadJ4)") (class "Default")
      (node (ref "U10") (pin "J4") (pinfunction "DQ17_J4") (pintype "passive"))
    )
    (net (code "113") (name "unconnected-(U10B-DQ18-PadK1)") (class "Default")
      (node (ref "U10") (pin "K1") (pinfunction "DQ18_K1") (pintype "passive"))
    )
    (net (code "114") (name "unconnected-(U10B-DQ19-PadJ2)") (class "Default")
      (node (ref "U10") (pin "J2") (pinfunction "DQ19_J2") (pintype "passive"))
    )
    (net (code "115") (name "unconnected-(U10B-DQ20-PadJ3)") (class "Default")
      (node (ref "U10") (pin "J3") (pinfunction "DQ20_J3") (pintype "passive"))
    )
    (net (code "116") (name "unconnected-(U10B-DQ21-PadJ1)") (class "Default")
      (node (ref "U10") (pin "J1") (pinfunction "DQ21_J1") (pintype "passive"))
    )
    (net (code "117") (name "unconnected-(U10B-DQ22-PadH2)") (class "Default")
      (node (ref "U10") (pin "H2") (pinfunction "DQ22_H2") (pintype "passive"))
    )
    (net (code "118") (name "unconnected-(U10B-DQ23-PadH3)") (class "Default")
      (node (ref "U10") (pin "H3") (pinfunction "DQ23_H3") (pintype "passive"))
    )
    (net (code "119") (name "unconnected-(U10B-DQ24-PadF4)") (class "Default")
      (node (ref "U10") (pin "F4") (pinfunction "DQ24_F4") (pintype "passive"))
    )
    (net (code "120") (name "unconnected-(U10B-DQ25-PadG2)") (class "Default")
      (node (ref "U10") (pin "G2") (pinfunction "DQ25_G2") (pintype "passive"))
    )
    (net (code "121") (name "unconnected-(U10B-DQ26-PadG3)") (class "Default")
      (node (ref "U10") (pin "G3") (pinfunction "DQ26_G3") (pintype "passive"))
    )
    (net (code "122") (name "unconnected-(U10B-DQ27-PadF3)") (class "Default")
      (node (ref "U10") (pin "F3") (pinfunction "DQ27_F3") (pintype "passive"))
    )
    (net (code "123") (name "unconnected-(U10B-GPIO45-PadF2)") (class "Default")
      (node (ref "U10") (pin "F2") (pinfunction "GPIO45_F2") (pintype "passive"))
    )
    (net (code "124") (name "unconnected-(U10C-DQ28-PadF5)") (class "Default")
      (node (ref "U10") (pin "F5") (pinfunction "DQ28_F5") (pintype "passive"))
    )
    (net (code "125") (name "unconnected-(U10C-DQ29-PadE1)") (class "Default")
      (node (ref "U10") (pin "E1") (pinfunction "DQ29_E1") (pintype "passive"))
    )
    (net (code "126") (name "unconnected-(U10C-DQ30-PadE5)") (class "Default")
      (node (ref "U10") (pin "E5") (pinfunction "DQ30_E5") (pintype "passive"))
    )
    (net (code "127") (name "unconnected-(U10C-DQ31-PadE4)") (class "Default")
      (node (ref "U10") (pin "E4") (pinfunction "DQ31_E4") (pintype "passive"))
    )
    (net (code "128") (name "unconnected-(U10C-I2S-CLK-PadD1)") (class "Default")
      (node (ref "U10") (pin "D1") (pinfunction "I2S-CLK_D1") (pintype "passive"))
    )
    (net (code "129") (name "unconnected-(U10C-I2S-MCLK-PadC4)") (class "Default")
      (node (ref "U10") (pin "C4") (pinfunction "I2S-MCLK_C4") (pintype "passive"))
    )
    (net (code "130") (name "unconnected-(U10C-I2S-SD-PadD2)") (class "Default")
      (node (ref "U10") (pin "D2") (pinfunction "I2S-SD_D2") (pintype "passive"))
    )
    (net (code "131") (name "unconnected-(U10C-I2S-WS-PadD3)") (class "Default")
      (node (ref "U10") (pin "D3") (pinfunction "I2S-WS_D3") (pintype "passive"))
    )
    (net (code "132") (name "unconnected-(U10D-NC-PadA11)") (class "Default")
      (node (ref "U10") (pin "A11") (pinfunction "NC_A11") (pintype "passive"))
    )
    (net (code "133") (name "unconnected-(U10E-CLKIN-PadD7)") (class "Default")
      (node (ref "U10") (pin "D7") (pinfunction "CLKIN_D7") (pintype "passive"))
    )
    (net (code "134") (name "unconnected-(U10F-TCK-PadF6)") (class "Default")
      (node (ref "U10") (pin "F6") (pinfunction "TCK_F6") (pintype "passive"))
    )
    (net (code "135") (name "unconnected-(U10F-TDI-PadE7)") (class "Default")
      (node (ref "U10") (pin "E7") (pinfunction "TDI_E7") (pintype "passive"))
    )
    (net (code "136") (name "unconnected-(U10F-TDO-PadC10)") (class "Default")
      (node (ref "U10") (pin "C10") (pinfunction "TDO_C10") (pintype "passive"))
    )
    (net (code "137") (name "unconnected-(U10F-TMS-PadE8)") (class "Default")
      (node (ref "U10") (pin "E8") (pinfunction "TMS_E8") (pintype "passive"))
    )
    (net (code "138") (name "unconnected-(U10F-TRST_N-PadB11)") (class "Default")
      (node (ref "U10") (pin "B11") (pinfunction "TRST_N_B11") (pintype "passive"))
    )
    (net (code "139") (name "unconnected-(U10H-I2C-GPIO60_CHARGER-DETECT-PadD11)") (class "Default")
      (node (ref "U10") (pin "D11") (pinfunction "I2C-GPIO60_CHARGER-DETECT_D11") (pintype "passive+no_connect"))
    )
    (net (code "140") (name "unconnected-(U11-DU1-Pad1)") (class "Default")
      (node (ref "U11") (pin "1") (pinfunction "DU1_1") (pintype "passive"))
    )
    (net (code "141") (name "unconnected-(U11-DU2-Pad2)") (class "Default")
      (node (ref "U11") (pin "2") (pinfunction "DU2_2") (pintype "passive"))
    )
    (net (code "142") (name "unconnected-(U11-E2-Pad3)") (class "Default")
      (node (ref "U11") (pin "3") (pinfunction "E2_3") (pintype "passive"))
    )
    (net (code "143") (name "unconnected-(U11-~{WC}-Pad7)") (class "Default")
      (node (ref "U11") (pin "7") (pinfunction "~{WC}_7") (pintype "passive"))
    )
    (net (code "144") (name "unconnected-(U12-NC-Pad1)") (class "Default")
      (node (ref "U12") (pin "1") (pinfunction "NC_1") (pintype "passive"))
    )
    (net (code "145") (name "unconnected-(U12-NC-Pad2)") (class "Default")
      (node (ref "U12") (pin "2") (pinfunction "NC_2") (pintype "passive"))
    )
    (net (code "146") (name "unconnected-(U12-NC-Pad3)") (class "Default")
      (node (ref "U12") (pin "3") (pinfunction "NC_3") (pintype "passive"))
    )
    (net (code "147") (name "unconnected-(U12-NC-Pad7)") (class "Default")
      (node (ref "U12") (pin "7") (pinfunction "NC_7") (pintype "passive"))
    )
  )
)
